# Wireless_thermometer_sensors.net
KiCad netlist of a schematic drawn in Altium Designer
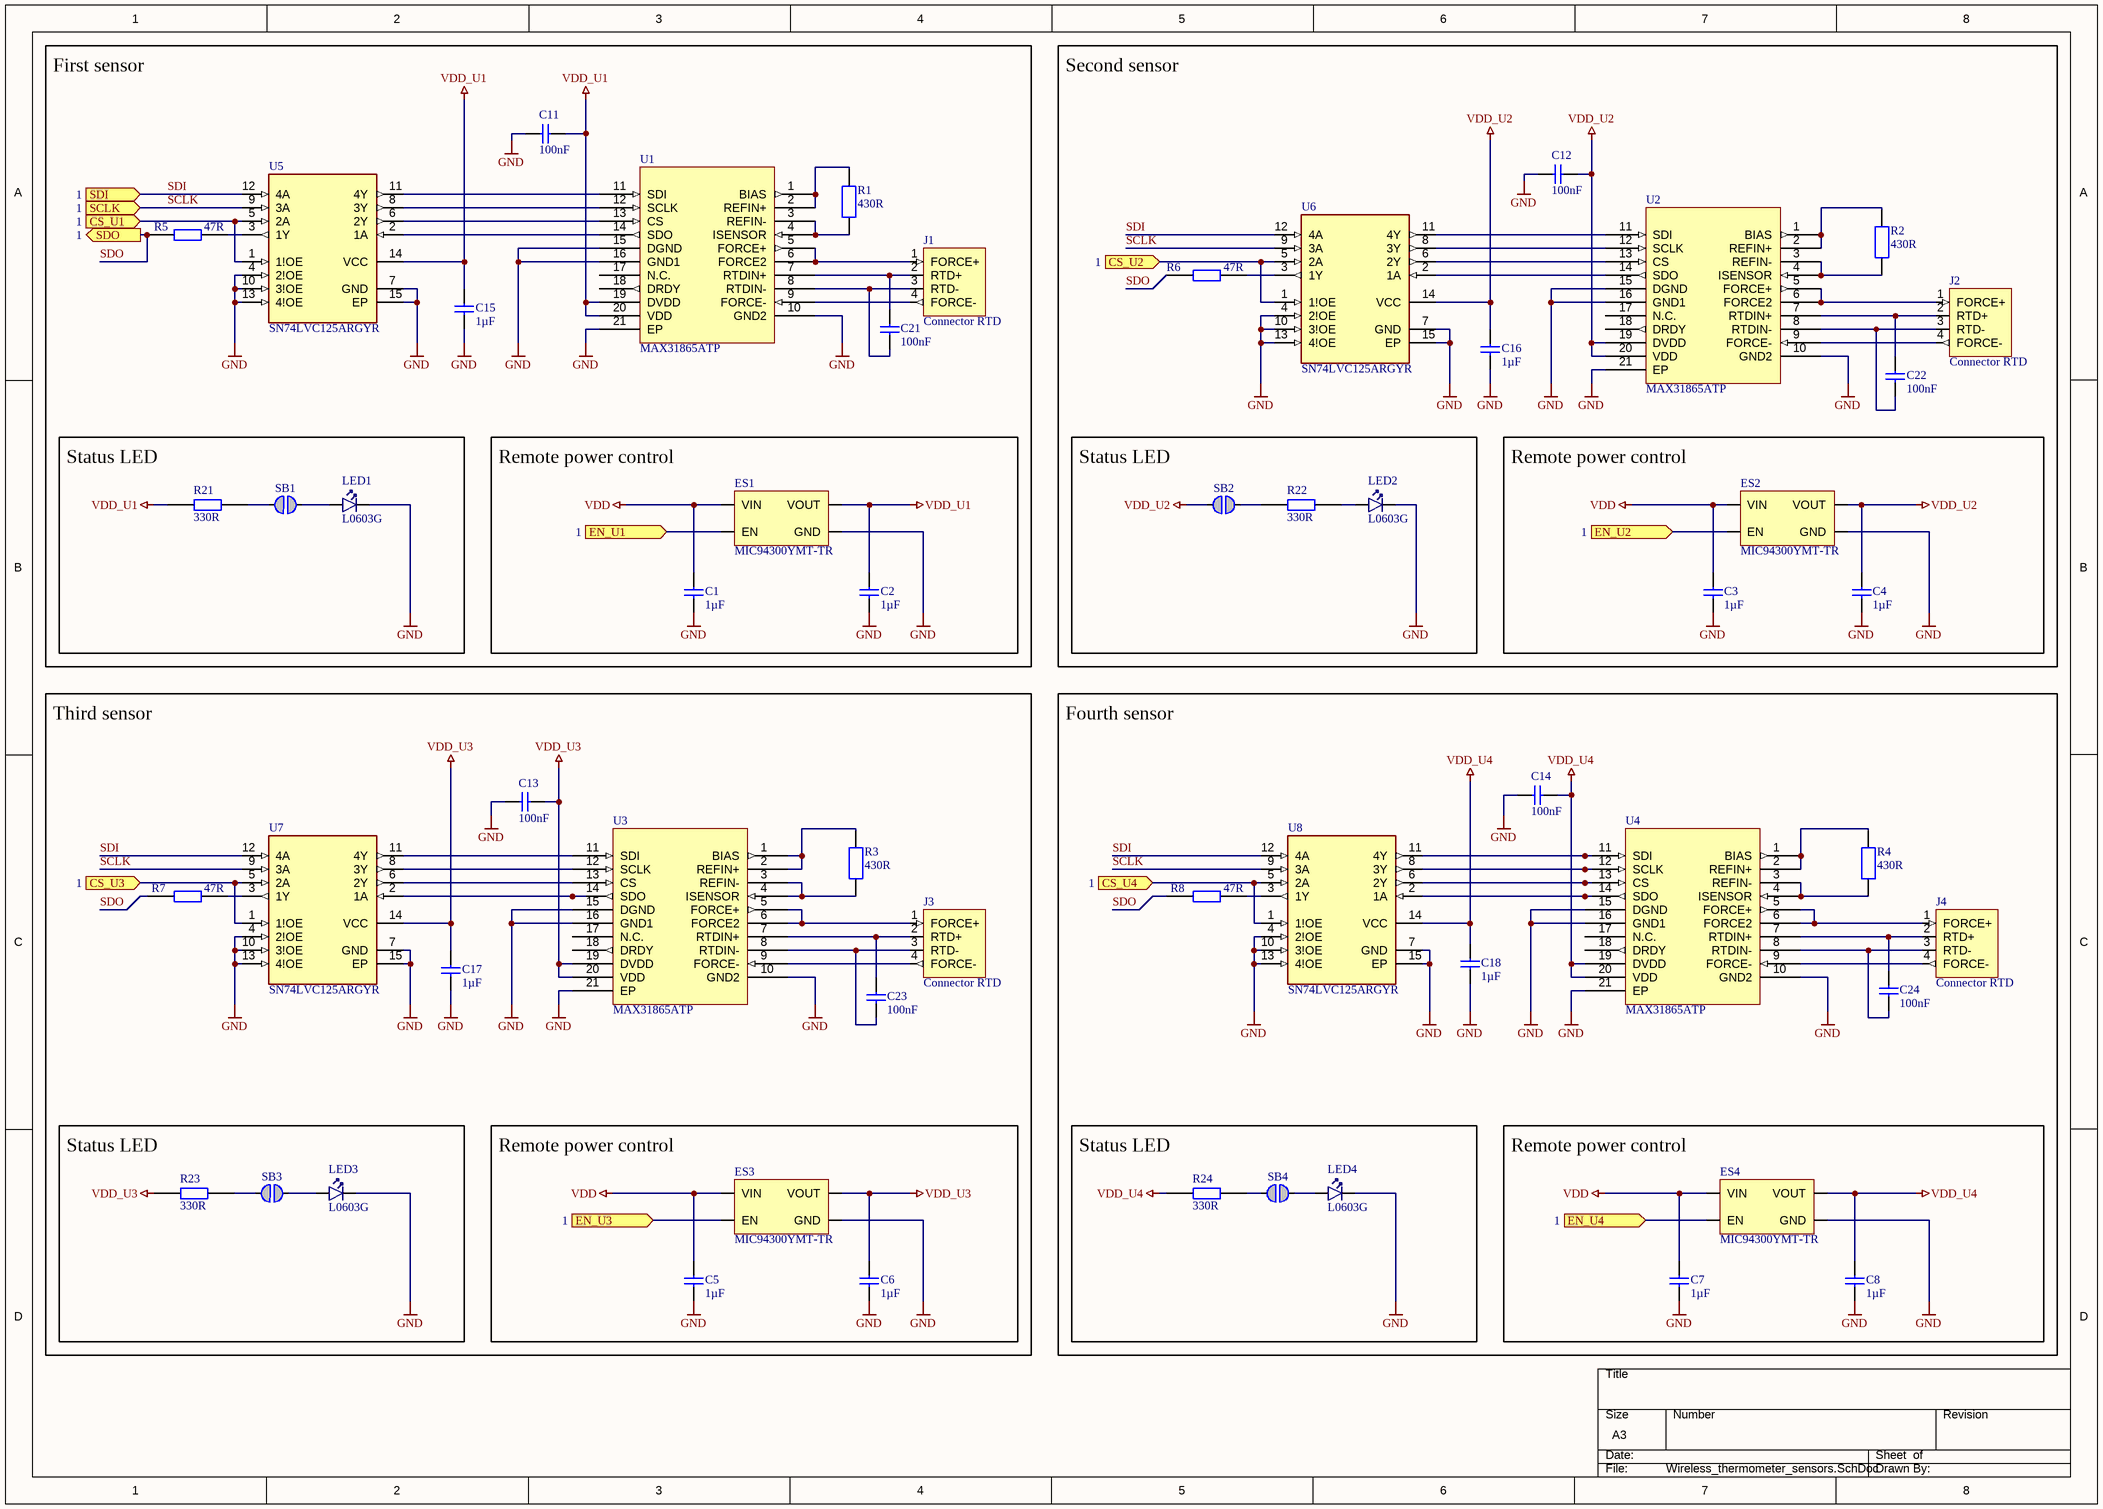
[diagram p0: Wireless_thermometer_sensors.SchDoc]

(export (version "E")
  (design (tool "Eeschema 10.0.6"))
  (components
    (comp (ref "C1")
      (value "1µF")
      (footprint "CAPC1005X04L")
      (description "Capacitor, X7R, ±10%")
      (fields (field (name "PART NUMBER") "C0402-1µ0") (field (name "PUBLISHER") "Nordic Semiconductor"))
      (libsource (lib "Remote_thermometer") (part "CAP_0402"))
    )
    (comp (ref "C2")
      (value "1µF")
      (footprint "CAPC1005X04L")
      (description "Capacitor, X7R, ±10%")
      (fields (field (name "PART NUMBER") "C0402-1µ0") (field (name "PUBLISHER") "Nordic Semiconductor"))
      (libsource (lib "Remote_thermometer") (part "CAP_0402"))
    )
    (comp (ref "C3")
      (value "1µF")
      (footprint "CAPC1005X04L")
      (description "Capacitor, X7R, ±10%")
      (fields (field (name "PART NUMBER") "C0402-1µ0") (field (name "PUBLISHER") "Nordic Semiconductor"))
      (libsource (lib "Remote_thermometer") (part "CAP_0402"))
    )
    (comp (ref "C4")
      (value "1µF")
      (footprint "CAPC1005X04L")
      (description "Capacitor, X7R, ±10%")
      (fields (field (name "PART NUMBER") "C0402-1µ0") (field (name "PUBLISHER") "Nordic Semiconductor"))
      (libsource (lib "Remote_thermometer") (part "CAP_0402"))
    )
    (comp (ref "C5")
      (value "1µF")
      (footprint "CAPC1005X04L")
      (description "Capacitor, X7R, ±10%")
      (fields (field (name "PART NUMBER") "C0402-1µ0") (field (name "PUBLISHER") "Nordic Semiconductor"))
      (libsource (lib "Remote_thermometer") (part "CAP_0402"))
    )
    (comp (ref "C6")
      (value "1µF")
      (footprint "CAPC1005X04L")
      (description "Capacitor, X7R, ±10%")
      (fields (field (name "PART NUMBER") "C0402-1µ0") (field (name "PUBLISHER") "Nordic Semiconductor"))
      (libsource (lib "Remote_thermometer") (part "CAP_0402"))
    )
    (comp (ref "C7")
      (value "1µF")
      (footprint "CAPC1005X04L")
      (description "Capacitor, X7R, ±10%")
      (fields (field (name "PART NUMBER") "C0402-1µ0") (field (name "PUBLISHER") "Nordic Semiconductor"))
      (libsource (lib "Remote_thermometer") (part "CAP_0402"))
    )
    (comp (ref "C8")
      (value "1µF")
      (footprint "CAPC1005X04L")
      (description "Capacitor, X7R, ±10%")
      (fields (field (name "PART NUMBER") "C0402-1µ0") (field (name "PUBLISHER") "Nordic Semiconductor"))
      (libsource (lib "Remote_thermometer") (part "CAP_0402"))
    )
    (comp (ref "C11")
      (value "100nF")
      (footprint "CAPC1005X04L")
      (description "Capacitor, X7R, ±10%")
      (fields (field (name "PART NUMBER") "C0402-1µ0") (field (name "PUBLISHER") "Nordic Semiconductor"))
      (libsource (lib "Remote_thermometer") (part "CAP_0402"))
    )
    (comp (ref "C12")
      (value "100nF")
      (footprint "CAPC1005X04L")
      (description "Capacitor, X7R, ±10%")
      (fields (field (name "PART NUMBER") "C0402-1µ0") (field (name "PUBLISHER") "Nordic Semiconductor"))
      (libsource (lib "Remote_thermometer") (part "CAP_0402"))
    )
    (comp (ref "C13")
      (value "100nF")
      (footprint "CAPC1005X04L")
      (description "Capacitor, X7R, ±10%")
      (fields (field (name "PART NUMBER") "C0402-1µ0") (field (name "PUBLISHER") "Nordic Semiconductor"))
      (libsource (lib "Remote_thermometer") (part "CAP_0402"))
    )
    (comp (ref "C14")
      (value "100nF")
      (footprint "CAPC1005X04L")
      (description "Capacitor, X7R, ±10%")
      (fields (field (name "PART NUMBER") "C0402-1µ0") (field (name "PUBLISHER") "Nordic Semiconductor"))
      (libsource (lib "Remote_thermometer") (part "CAP_0402"))
    )
    (comp (ref "C15")
      (value "1µF")
      (footprint "CAPC1005X04L")
      (description "Capacitor, X7R, ±10%")
      (fields (field (name "PART NUMBER") "C0402-1µ0") (field (name "PUBLISHER") "Nordic Semiconductor"))
      (libsource (lib "Remote_thermometer") (part "CAP_0402"))
    )
    (comp (ref "C16")
      (value "1µF")
      (footprint "CAPC1005X04L")
      (description "Capacitor, X7R, ±10%")
      (fields (field (name "PART NUMBER") "C0402-1µ0") (field (name "PUBLISHER") "Nordic Semiconductor"))
      (libsource (lib "Remote_thermometer") (part "CAP_0402"))
    )
    (comp (ref "C17")
      (value "1µF")
      (footprint "CAPC1005X04L")
      (description "Capacitor, X7R, ±10%")
      (fields (field (name "PART NUMBER") "C0402-1µ0") (field (name "PUBLISHER") "Nordic Semiconductor"))
      (libsource (lib "Remote_thermometer") (part "CAP_0402"))
    )
    (comp (ref "C18")
      (value "1µF")
      (footprint "CAPC1005X04L")
      (description "Capacitor, X7R, ±10%")
      (fields (field (name "PART NUMBER") "C0402-1µ0") (field (name "PUBLISHER") "Nordic Semiconductor"))
      (libsource (lib "Remote_thermometer") (part "CAP_0402"))
    )
    (comp (ref "C21")
      (value "100nF")
      (footprint "CAPC1005X04L")
      (description "Capacitor, X7R, ±10%")
      (fields (field (name "PART NUMBER") "C0402-1µ0") (field (name "PUBLISHER") "Nordic Semiconductor"))
      (libsource (lib "Remote_thermometer") (part "CAP_0402"))
    )
    (comp (ref "C22")
      (value "100nF")
      (footprint "CAPC1005X04L")
      (description "Capacitor, X7R, ±10%")
      (fields (field (name "PART NUMBER") "C0402-1µ0") (field (name "PUBLISHER") "Nordic Semiconductor"))
      (libsource (lib "Remote_thermometer") (part "CAP_0402"))
    )
    (comp (ref "C23")
      (value "100nF")
      (footprint "CAPC1005X04L")
      (description "Capacitor, X7R, ±10%")
      (fields (field (name "PART NUMBER") "C0402-1µ0") (field (name "PUBLISHER") "Nordic Semiconductor"))
      (libsource (lib "Remote_thermometer") (part "CAP_0402"))
    )
    (comp (ref "C24")
      (value "100nF")
      (footprint "CAPC1005X04L")
      (description "Capacitor, X7R, ±10%")
      (fields (field (name "PART NUMBER") "C0402-1µ0") (field (name "PUBLISHER") "Nordic Semiconductor"))
      (libsource (lib "Remote_thermometer") (part "CAP_0402"))
    )
    (comp (ref "ES1")
      (value "MIC94300YMT-TR")
      (footprint "MIC94300YMT-TR")
      (description "MIC94300 Series Single 3.6 V 200 mA Ripple Blocker Technology Load Switch -MLF-4")
      (fields (field (name "MANUFACTURER") "Microchip"))
      (libsource (lib "Remote_thermometer") (part "MIC94300YMT-TR"))
    )
    (comp (ref "ES2")
      (value "MIC94300YMT-TR")
      (footprint "MIC94300YMT-TR")
      (description "MIC94300 Series Single 3.6 V 200 mA Ripple Blocker Technology Load Switch -MLF-4")
      (fields (field (name "MANUFACTURER") "Microchip"))
      (libsource (lib "Remote_thermometer") (part "MIC94300YMT-TR"))
    )
    (comp (ref "ES3")
      (value "MIC94300YMT-TR")
      (footprint "MIC94300YMT-TR")
      (description "MIC94300 Series Single 3.6 V 200 mA Ripple Blocker Technology Load Switch -MLF-4")
      (fields (field (name "MANUFACTURER") "Microchip"))
      (libsource (lib "Remote_thermometer") (part "MIC94300YMT-TR"))
    )
    (comp (ref "ES4")
      (value "MIC94300YMT-TR")
      (footprint "MIC94300YMT-TR")
      (description "MIC94300 Series Single 3.6 V 200 mA Ripple Blocker Technology Load Switch -MLF-4")
      (fields (field (name "MANUFACTURER") "Microchip"))
      (libsource (lib "Remote_thermometer") (part "MIC94300YMT-TR"))
    )
    (comp (ref "J1")
      (value "Connector RTD")
      (footprint "CON-RTD")
      (libsource (lib "Remote_thermometer") (part "CON-RTD"))
    )
    (comp (ref "J2")
      (value "Connector RTD")
      (footprint "CON-RTD")
      (libsource (lib "Remote_thermometer") (part "CON-RTD"))
    )
    (comp (ref "J3")
      (value "Connector RTD")
      (footprint "CON-RTD")
      (libsource (lib "Remote_thermometer") (part "CON-RTD"))
    )
    (comp (ref "J4")
      (value "Connector RTD")
      (footprint "CON-RTD")
      (libsource (lib "Remote_thermometer") (part "CON-RTD"))
    )
    (comp (ref "LED1")
      (value "L0603G")
      (footprint "LED_0603_G")
      (description "LED, Green, 0603, 573nm, Vf=2.0V, 24mcd, - 40 to +85°C")
      (fields
        (field (name "PART NUMBER") "VS 25C7M5")
        (field (name "MANUFACTURER") "Victory Electronics")
        (field (name "PUBLISHER") "Nordic Semiconductor")
      )
      (libsource (lib "Remote_thermometer") (part "D{colon}LED"))
    )
    (comp (ref "LED2")
      (value "L0603G")
      (footprint "LED_0603_G")
      (description "LED, Green, 0603, 573nm, Vf=2.0V, 24mcd, - 40 to +85°C")
      (fields
        (field (name "PART NUMBER") "VS 25C7M5")
        (field (name "MANUFACTURER") "Victory Electronics")
        (field (name "PUBLISHER") "Nordic Semiconductor")
      )
      (libsource (lib "Remote_thermometer") (part "D{colon}LED"))
    )
    (comp (ref "LED3")
      (value "L0603G")
      (footprint "LED_0603_G")
      (description "LED, Green, 0603, 573nm, Vf=2.0V, 24mcd, - 40 to +85°C")
      (fields
        (field (name "PART NUMBER") "VS 25C7M5")
        (field (name "MANUFACTURER") "Victory Electronics")
        (field (name "PUBLISHER") "Nordic Semiconductor")
      )
      (libsource (lib "Remote_thermometer") (part "D{colon}LED"))
    )
    (comp (ref "LED4")
      (value "L0603G")
      (footprint "LED_0603_G")
      (description "LED, Green, 0603, 573nm, Vf=2.0V, 24mcd, - 40 to +85°C")
      (fields
        (field (name "PART NUMBER") "VS 25C7M5")
        (field (name "MANUFACTURER") "Victory Electronics")
        (field (name "PUBLISHER") "Nordic Semiconductor")
      )
      (libsource (lib "Remote_thermometer") (part "D{colon}LED"))
    )
    (comp (ref "R1")
      (value "430R")
      (footprint "RESR1608X06")
      (description "Resistor")
      (fields (field (name "PART NUMBER") "R0603-430R") (field (name "PUBLISHER") "Nordic Semiconductor"))
      (libsource (lib "Remote_thermometer") (part "RES_0603"))
    )
    (comp (ref "R2")
      (value "430R")
      (footprint "RESR1608X06")
      (description "Resistor")
      (fields (field (name "PART NUMBER") "R0603-430R") (field (name "PUBLISHER") "Nordic Semiconductor"))
      (libsource (lib "Remote_thermometer") (part "RES_0603"))
    )
    (comp (ref "R3")
      (value "430R")
      (footprint "RESR1608X06")
      (description "Resistor")
      (fields (field (name "PART NUMBER") "R0603-430R") (field (name "PUBLISHER") "Nordic Semiconductor"))
      (libsource (lib "Remote_thermometer") (part "RES_0603"))
    )
    (comp (ref "R4")
      (value "430R")
      (footprint "RESR1608X06")
      (description "Resistor")
      (fields (field (name "PART NUMBER") "R0603-430R") (field (name "PUBLISHER") "Nordic Semiconductor"))
      (libsource (lib "Remote_thermometer") (part "RES_0603"))
    )
    (comp (ref "R5")
      (value "47R")
      (footprint "RESC1005X04L")
      (description "Resistor")
      (fields (field (name "PART NUMBER") "R0603-430R") (field (name "PUBLISHER") "Nordic Semiconductor"))
      (libsource (lib "Remote_thermometer") (part "RES_0402"))
    )
    (comp (ref "R6")
      (value "47R")
      (footprint "RESC1005X04L")
      (description "Resistor")
      (fields (field (name "PART NUMBER") "R0603-430R") (field (name "PUBLISHER") "Nordic Semiconductor"))
      (libsource (lib "Remote_thermometer") (part "RES_0402"))
    )
    (comp (ref "R7")
      (value "47R")
      (footprint "RESC1005X04L")
      (description "Resistor")
      (fields (field (name "PART NUMBER") "R0603-430R") (field (name "PUBLISHER") "Nordic Semiconductor"))
      (libsource (lib "Remote_thermometer") (part "RES_0402"))
    )
    (comp (ref "R8")
      (value "47R")
      (footprint "RESC1005X04L")
      (description "Resistor")
      (fields (field (name "PART NUMBER") "R0603-430R") (field (name "PUBLISHER") "Nordic Semiconductor"))
      (libsource (lib "Remote_thermometer") (part "RES_0402"))
    )
    (comp (ref "R21")
      (value "330R")
      (footprint "RESC1005X04L")
      (description "Resistor")
      (fields (field (name "PART NUMBER") "R0603-430R") (field (name "PUBLISHER") "Nordic Semiconductor"))
      (libsource (lib "Remote_thermometer") (part "RES_0402"))
    )
    (comp (ref "R22")
      (value "330R")
      (footprint "RESC1005X04L")
      (description "Resistor")
      (fields (field (name "PART NUMBER") "R0603-430R") (field (name "PUBLISHER") "Nordic Semiconductor"))
      (libsource (lib "Remote_thermometer") (part "RES_0402"))
    )
    (comp (ref "R23")
      (value "330R")
      (footprint "RESC1005X04L")
      (description "Resistor")
      (fields (field (name "PART NUMBER") "R0603-430R") (field (name "PUBLISHER") "Nordic Semiconductor"))
      (libsource (lib "Remote_thermometer") (part "RES_0402"))
    )
    (comp (ref "R24")
      (value "330R")
      (footprint "RESC1005X04L")
      (description "Resistor")
      (fields (field (name "PART NUMBER") "R0603-430R") (field (name "PUBLISHER") "Nordic Semiconductor"))
      (libsource (lib "Remote_thermometer") (part "RES_0402"))
    )
    (comp (ref "SB1")
      (value "Solderbridge")
      (footprint "Solderbridge")
      (fields (field (name "PUBLISHER") "Nordic Semiconductor"))
      (libsource (lib "Remote_thermometer") (part "SOLDERBRIDGE"))
    )
    (comp (ref "SB2")
      (value "Solderbridge")
      (footprint "Solderbridge")
      (fields (field (name "PUBLISHER") "Nordic Semiconductor"))
      (libsource (lib "Remote_thermometer") (part "SOLDERBRIDGE"))
    )
    (comp (ref "SB3")
      (value "Solderbridge")
      (footprint "Solderbridge")
      (fields (field (name "PUBLISHER") "Nordic Semiconductor"))
      (libsource (lib "Remote_thermometer") (part "SOLDERBRIDGE"))
    )
    (comp (ref "SB4")
      (value "Solderbridge")
      (footprint "Solderbridge")
      (fields (field (name "PUBLISHER") "Nordic Semiconductor"))
      (libsource (lib "Remote_thermometer") (part "SOLDERBRIDGE"))
    )
    (comp (ref "U1")
      (value "MAX31865ATP")
      (footprint "21-0140L_T2055-5_MXM-L")
      (description "Circuit Protection Misc Resistance Temperature Detector to Digital Converter")
      (fields (field (name "MANUFACTURER") "Maxim") (field (name "MANUFACTURER PART NUMBER") "MAX31865ATP+T"))
      (libsource (lib "Remote_thermometer") (part "MAX31865ATP"))
    )
    (comp (ref "U2")
      (value "MAX31865ATP")
      (footprint "21-0140L_T2055-5_MXM-L")
      (description "Circuit Protection Misc Resistance Temperature Detector to Digital Converter")
      (fields (field (name "MANUFACTURER") "Maxim") (field (name "MANUFACTURER PART NUMBER") "MAX31865ATP+T"))
      (libsource (lib "Remote_thermometer") (part "MAX31865ATP"))
    )
    (comp (ref "U3")
      (value "MAX31865ATP")
      (footprint "21-0140L_T2055-5_MXM-L")
      (description "Circuit Protection Misc Resistance Temperature Detector to Digital Converter")
      (fields (field (name "MANUFACTURER") "Maxim") (field (name "MANUFACTURER PART NUMBER") "MAX31865ATP+T"))
      (libsource (lib "Remote_thermometer") (part "MAX31865ATP"))
    )
    (comp (ref "U4")
      (value "MAX31865ATP")
      (footprint "21-0140L_T2055-5_MXM-L")
      (description "Circuit Protection Misc Resistance Temperature Detector to Digital Converter")
      (fields (field (name "MANUFACTURER") "Maxim") (field (name "MANUFACTURER PART NUMBER") "MAX31865ATP+T"))
      (libsource (lib "Remote_thermometer") (part "MAX31865ATP"))
    )
    (comp (ref "U5")
      (value "SN74LVC125ARGYR")
      (footprint "QFN50P350X350X100-15N")
      (description "Quadruple Bus Buffer Gate With 3-State Outputs 14-VQFN -40 to 125")
      (libsource (lib "Remote_thermometer") (part "SN74LVC125ARGYR"))
    )
    (comp (ref "U6")
      (value "SN74LVC125ARGYR")
      (footprint "QFN50P350X350X100-15N")
      (description "Quadruple Bus Buffer Gate With 3-State Outputs 14-VQFN -40 to 125")
      (libsource (lib "Remote_thermometer") (part "SN74LVC125ARGYR"))
    )
    (comp (ref "U7")
      (value "SN74LVC125ARGYR")
      (footprint "QFN50P350X350X100-15N")
      (description "Quadruple Bus Buffer Gate With 3-State Outputs 14-VQFN -40 to 125")
      (libsource (lib "Remote_thermometer") (part "SN74LVC125ARGYR"))
    )
    (comp (ref "U8")
      (value "SN74LVC125ARGYR")
      (footprint "QFN50P350X350X100-15N")
      (description "Quadruple Bus Buffer Gate With 3-State Outputs 14-VQFN -40 to 125")
      (libsource (lib "Remote_thermometer") (part "SN74LVC125ARGYR"))
    )
  )
  (nets
    (net (code "1") (name "/CS_U1") (class "Default")
      (node (ref "U5") (pin "1") (pinfunction "1!OE_1") (pintype "input"))
      (node (ref "U5") (pin "5") (pinfunction "2A_5") (pintype "input"))
    )
    (net (code "2") (name "/CS_U2") (class "Default")
      (node (ref "U6") (pin "1") (pinfunction "1!OE_1") (pintype "input"))
      (node (ref "U6") (pin "5") (pinfunction "2A_5") (pintype "input"))
    )
    (net (code "3") (name "/CS_U3") (class "Default")
      (node (ref "U7") (pin "1") (pinfunction "1!OE_1") (pintype "input"))
      (node (ref "U7") (pin "5") (pinfunction "2A_5") (pintype "input"))
    )
    (net (code "4") (name "/CS_U4") (class "Default")
      (node (ref "U8") (pin "1") (pinfunction "1!OE_1") (pintype "input"))
      (node (ref "U8") (pin "5") (pinfunction "2A_5") (pintype "input"))
    )
    (net (code "5") (name "/EN_U1") (class "Default")
      (node (ref "ES1") (pin "1") (pinfunction "EN_1") (pintype "passive"))
    )
    (net (code "6") (name "/EN_U2") (class "Default")
      (node (ref "ES2") (pin "1") (pinfunction "EN_1") (pintype "passive"))
    )
    (net (code "7") (name "/EN_U3") (class "Default")
      (node (ref "ES3") (pin "1") (pinfunction "EN_1") (pintype "passive"))
    )
    (net (code "8") (name "/EN_U4") (class "Default")
      (node (ref "ES4") (pin "1") (pinfunction "EN_1") (pintype "passive"))
    )
    (net (code "9") (name "/SCLK") (class "Default")
      (node (ref "U5") (pin "9") (pinfunction "3A_9") (pintype "input"))
      (node (ref "U6") (pin "9") (pinfunction "3A_9") (pintype "input"))
      (node (ref "U7") (pin "9") (pinfunction "3A_9") (pintype "input"))
      (node (ref "U8") (pin "9") (pinfunction "3A_9") (pintype "input"))
    )
    (net (code "10") (name "/SDI") (class "Default")
      (node (ref "U5") (pin "12") (pinfunction "4A_12") (pintype "input"))
      (node (ref "U6") (pin "12") (pinfunction "4A_12") (pintype "input"))
      (node (ref "U7") (pin "12") (pinfunction "4A_12") (pintype "input"))
      (node (ref "U8") (pin "12") (pinfunction "4A_12") (pintype "input"))
    )
    (net (code "11") (name "/SDO") (class "Default")
      (node (ref "R5") (pin "1") (pinfunction "1_1") (pintype "passive"))
      (node (ref "R6") (pin "1") (pinfunction "1_1") (pintype "passive"))
      (node (ref "R7") (pin "1") (pinfunction "1_1") (pintype "passive"))
      (node (ref "R8") (pin "1") (pinfunction "1_1") (pintype "passive"))
    )
    (net (code "12") (name "GND") (class "Default")
      (node (ref "C1") (pin "1") (pinfunction "1_1") (pintype "passive"))
      (node (ref "C11") (pin "1") (pinfunction "1_1") (pintype "passive"))
      (node (ref "C12") (pin "1") (pinfunction "1_1") (pintype "passive"))
      (node (ref "C13") (pin "2") (pinfunction "2_2") (pintype "passive"))
      (node (ref "C14") (pin "1") (pinfunction "1_1") (pintype "passive"))
      (node (ref "C15") (pin "1") (pinfunction "1_1") (pintype "passive"))
      (node (ref "C16") (pin "1") (pinfunction "1_1") (pintype "passive"))
      (node (ref "C17") (pin "1") (pinfunction "1_1") (pintype "passive"))
      (node (ref "C18") (pin "1") (pinfunction "1_1") (pintype "passive"))
      (node (ref "C2") (pin "1") (pinfunction "1_1") (pintype "passive"))
      (node (ref "C3") (pin "1") (pinfunction "1_1") (pintype "passive"))
      (node (ref "C4") (pin "1") (pinfunction "1_1") (pintype "passive"))
      (node (ref "C5") (pin "1") (pinfunction "1_1") (pintype "passive"))
      (node (ref "C6") (pin "1") (pinfunction "1_1") (pintype "passive"))
      (node (ref "C7") (pin "1") (pinfunction "1_1") (pintype "passive"))
      (node (ref "C8") (pin "1") (pinfunction "1_1") (pintype "passive"))
      (node (ref "ES1") (pin "2") (pinfunction "GND_2") (pintype "passive"))
      (node (ref "ES2") (pin "2") (pinfunction "GND_2") (pintype "passive"))
      (node (ref "ES3") (pin "2") (pinfunction "GND_2") (pintype "passive"))
      (node (ref "ES4") (pin "2") (pinfunction "GND_2") (pintype "passive"))
      (node (ref "LED1") (pin "1") (pinfunction "C_1") (pintype "passive"))
      (node (ref "LED2") (pin "1") (pinfunction "C_1") (pintype "passive"))
      (node (ref "LED3") (pin "1") (pinfunction "C_1") (pintype "passive"))
      (node (ref "LED4") (pin "1") (pinfunction "C_1") (pintype "passive"))
      (node (ref "U1") (pin "10") (pinfunction "GND2_10") (pintype "passive"))
      (node (ref "U1") (pin "15") (pinfunction "DGND_15") (pintype "passive"))
      (node (ref "U1") (pin "16") (pinfunction "GND1_16") (pintype "passive"))
      (node (ref "U1") (pin "21") (pinfunction "EP_21") (pintype "passive"))
      (node (ref "U2") (pin "10") (pinfunction "GND2_10") (pintype "passive"))
      (node (ref "U2") (pin "15") (pinfunction "DGND_15") (pintype "passive"))
      (node (ref "U2") (pin "16") (pinfunction "GND1_16") (pintype "passive"))
      (node (ref "U2") (pin "21") (pinfunction "EP_21") (pintype "passive"))
      (node (ref "U3") (pin "10") (pinfunction "GND2_10") (pintype "passive"))
      (node (ref "U3") (pin "15") (pinfunction "DGND_15") (pintype "passive"))
      (node (ref "U3") (pin "16") (pinfunction "GND1_16") (pintype "passive"))
      (node (ref "U3") (pin "21") (pinfunction "EP_21") (pintype "passive"))
      (node (ref "U4") (pin "10") (pinfunction "GND2_10") (pintype "passive"))
      (node (ref "U4") (pin "15") (pinfunction "DGND_15") (pintype "passive"))
      (node (ref "U4") (pin "16") (pinfunction "GND1_16") (pintype "passive"))
      (node (ref "U4") (pin "21") (pinfunction "EP_21") (pintype "passive"))
      (node (ref "U5") (pin "10") (pinfunction "3!OE_10") (pintype "input"))
      (node (ref "U5") (pin "13") (pinfunction "4!OE_13") (pintype "input"))
      (node (ref "U5") (pin "15") (pinfunction "EP_15") (pintype "power_in"))
      (node (ref "U5") (pin "4") (pinfunction "2!OE_4") (pintype "input"))
      (node (ref "U5") (pin "7") (pinfunction "GND_7") (pintype "power_in"))
      (node (ref "U6") (pin "10") (pinfunction "3!OE_10") (pintype "input"))
      (node (ref "U6") (pin "13") (pinfunction "4!OE_13") (pintype "input"))
      (node (ref "U6") (pin "15") (pinfunction "EP_15") (pintype "power_in"))
      (node (ref "U6") (pin "4") (pinfunction "2!OE_4") (pintype "input"))
      (node (ref "U6") (pin "7") (pinfunction "GND_7") (pintype "power_in"))
      (node (ref "U7") (pin "10") (pinfunction "3!OE_10") (pintype "input"))
      (node (ref "U7") (pin "13") (pinfunction "4!OE_13") (pintype "input"))
      (node (ref "U7") (pin "15") (pinfunction "EP_15") (pintype "power_in"))
      (node (ref "U7") (pin "4") (pinfunction "2!OE_4") (pintype "input"))
      (node (ref "U7") (pin "7") (pinfunction "GND_7") (pintype "power_in"))
      (node (ref "U8") (pin "10") (pinfunction "3!OE_10") (pintype "input"))
      (node (ref "U8") (pin "13") (pinfunction "4!OE_13") (pintype "input"))
      (node (ref "U8") (pin "15") (pinfunction "EP_15") (pintype "power_in"))
      (node (ref "U8") (pin "4") (pinfunction "2!OE_4") (pintype "input"))
      (node (ref "U8") (pin "7") (pinfunction "GND_7") (pintype "power_in"))
    )
    (net (code "13") (name "Net-(J1-FORCE+)") (class "Default")
      (node (ref "J1") (pin "1") (pinfunction "FORCE+_1") (pintype "input"))
      (node (ref "U1") (pin "5") (pinfunction "FORCE+_5") (pintype "output"))
      (node (ref "U1") (pin "6") (pinfunction "FORCE2_6") (pintype "passive"))
    )
    (net (code "14") (name "Net-(J1-FORCE-)") (class "Default")
      (node (ref "J1") (pin "4") (pinfunction "FORCE-_4") (pintype "output"))
      (node (ref "U1") (pin "9") (pinfunction "FORCE-_9") (pintype "input"))
    )
    (net (code "15") (name "Net-(J1-RTD+)") (class "Default")
      (node (ref "C21") (pin "2") (pinfunction "2_2") (pintype "passive"))
      (node (ref "J1") (pin "2") (pinfunction "RTD+_2") (pintype "passive"))
      (node (ref "U1") (pin "7") (pinfunction "RTDIN+_7") (pintype "passive"))
    )
    (net (code "16") (name "Net-(J1-RTD-)") (class "Default")
      (node (ref "C21") (pin "1") (pinfunction "1_1") (pintype "passive"))
      (node (ref "J1") (pin "3") (pinfunction "RTD-_3") (pintype "passive"))
      (node (ref "U1") (pin "8") (pinfunction "RTDIN-_8") (pintype "passive"))
    )
    (net (code "17") (name "Net-(J2-FORCE+)") (class "Default")
      (node (ref "J2") (pin "1") (pinfunction "FORCE+_1") (pintype "input"))
      (node (ref "U2") (pin "5") (pinfunction "FORCE+_5") (pintype "output"))
      (node (ref "U2") (pin "6") (pinfunction "FORCE2_6") (pintype "passive"))
    )
    (net (code "18") (name "Net-(J2-FORCE-)") (class "Default")
      (node (ref "J2") (pin "4") (pinfunction "FORCE-_4") (pintype "output"))
      (node (ref "U2") (pin "9") (pinfunction "FORCE-_9") (pintype "input"))
    )
    (net (code "19") (name "Net-(J2-RTD+)") (class "Default")
      (node (ref "C22") (pin "2") (pinfunction "2_2") (pintype "passive"))
      (node (ref "J2") (pin "2") (pinfunction "RTD+_2") (pintype "passive"))
      (node (ref "U2") (pin "7") (pinfunction "RTDIN+_7") (pintype "passive"))
    )
    (net (code "20") (name "Net-(J2-RTD-)") (class "Default")
      (node (ref "C22") (pin "1") (pinfunction "1_1") (pintype "passive"))
      (node (ref "J2") (pin "3") (pinfunction "RTD-_3") (pintype "passive"))
      (node (ref "U2") (pin "8") (pinfunction "RTDIN-_8") (pintype "passive"))
    )
    (net (code "21") (name "Net-(J3-FORCE+)") (class "Default")
      (node (ref "J3") (pin "1") (pinfunction "FORCE+_1") (pintype "input"))
      (node (ref "U3") (pin "5") (pinfunction "FORCE+_5") (pintype "output"))
      (node (ref "U3") (pin "6") (pinfunction "FORCE2_6") (pintype "passive"))
    )
    (net (code "22") (name "Net-(J3-FORCE-)") (class "Default")
      (node (ref "J3") (pin "4") (pinfunction "FORCE-_4") (pintype "output"))
      (node (ref "U3") (pin "9") (pinfunction "FORCE-_9") (pintype "input"))
    )
    (net (code "23") (name "Net-(J3-RTD+)") (class "Default")
      (node (ref "C23") (pin "2") (pinfunction "2_2") (pintype "passive"))
      (node (ref "J3") (pin "2") (pinfunction "RTD+_2") (pintype "passive"))
      (node (ref "U3") (pin "7") (pinfunction "RTDIN+_7") (pintype "passive"))
    )
    (net (code "24") (name "Net-(J3-RTD-)") (class "Default")
      (node (ref "C23") (pin "1") (pinfunction "1_1") (pintype "passive"))
      (node (ref "J3") (pin "3") (pinfunction "RTD-_3") (pintype "passive"))
      (node (ref "U3") (pin "8") (pinfunction "RTDIN-_8") (pintype "passive"))
    )
    (net (code "25") (name "Net-(J4-FORCE+)") (class "Default")
      (node (ref "J4") (pin "1") (pinfunction "FORCE+_1") (pintype "input"))
      (node (ref "U4") (pin "5") (pinfunction "FORCE+_5") (pintype "output"))
      (node (ref "U4") (pin "6") (pinfunction "FORCE2_6") (pintype "passive"))
    )
    (net (code "26") (name "Net-(J4-FORCE-)") (class "Default")
      (node (ref "J4") (pin "4") (pinfunction "FORCE-_4") (pintype "output"))
      (node (ref "U4") (pin "9") (pinfunction "FORCE-_9") (pintype "input"))
    )
    (net (code "27") (name "Net-(J4-RTD+)") (class "Default")
      (node (ref "C24") (pin "2") (pinfunction "2_2") (pintype "passive"))
      (node (ref "J4") (pin "2") (pinfunction "RTD+_2") (pintype "passive"))
      (node (ref "U4") (pin "7") (pinfunction "RTDIN+_7") (pintype "passive"))
    )
    (net (code "28") (name "Net-(J4-RTD-)") (class "Default")
      (node (ref "C24") (pin "1") (pinfunction "1_1") (pintype "passive"))
      (node (ref "J4") (pin "3") (pinfunction "RTD-_3") (pintype "passive"))
      (node (ref "U4") (pin "8") (pinfunction "RTDIN-_8") (pintype "passive"))
    )
    (net (code "29") (name "Net-(LED1-A)") (class "Default")
      (node (ref "LED1") (pin "2") (pinfunction "A_2") (pintype "passive"))
      (node (ref "SB1") (pin "1") (pinfunction "0_1") (pintype "passive"))
    )
    (net (code "30") (name "Net-(LED2-A)") (class "Default")
      (node (ref "LED2") (pin "2") (pinfunction "A_2") (pintype "passive"))
      (node (ref "R22") (pin "2") (pinfunction "2_2") (pintype "passive"))
    )
    (net (code "31") (name "Net-(LED3-A)") (class "Default")
      (node (ref "LED3") (pin "2") (pinfunction "A_2") (pintype "passive"))
      (node (ref "SB3") (pin "1") (pinfunction "0_1") (pintype "passive"))
    )
    (net (code "32") (name "Net-(LED4-A)") (class "Default")
      (node (ref "LED4") (pin "2") (pinfunction "A_2") (pintype "passive"))
      (node (ref "SB4") (pin "1") (pinfunction "0_1") (pintype "passive"))
    )
    (net (code "33") (name "Net-(SB1-1)") (class "Default")
      (node (ref "R21") (pin "2") (pinfunction "2_2") (pintype "passive"))
      (node (ref "SB1") (pin "2") (pinfunction "1_2") (pintype "passive"))
    )
    (net (code "34") (name "Net-(SB2-0)") (class "Default")
      (node (ref "R22") (pin "1") (pinfunction "1_1") (pintype "passive"))
      (node (ref "SB2") (pin "1") (pinfunction "0_1") (pintype "passive"))
    )
    (net (code "35") (name "Net-(SB3-1)") (class "Default")
      (node (ref "R23") (pin "2") (pinfunction "2_2") (pintype "passive"))
      (node (ref "SB3") (pin "2") (pinfunction "1_2") (pintype "passive"))
    )
    (net (code "36") (name "Net-(SB4-1)") (class "Default")
      (node (ref "R24") (pin "2") (pinfunction "2_2") (pintype "passive"))
      (node (ref "SB4") (pin "2") (pinfunction "1_2") (pintype "passive"))
    )
    (net (code "37") (name "Net-(U1-BIAS)") (class "Default")
      (node (ref "R1") (pin "2") (pinfunction "2_2") (pintype "passive"))
      (node (ref "U1") (pin "1") (pinfunction "BIAS_1") (pintype "output"))
      (node (ref "U1") (pin "2") (pinfunction "REFIN+_2") (pintype "passive"))
    )
    (net (code "38") (name "Net-(U1-CS)") (class "Default")
      (node (ref "U1") (pin "13") (pinfunction "CS_13") (pintype "input"))
      (node (ref "U5") (pin "6") (pinfunction "2Y_6") (pintype "output"))
    )
    (net (code "39") (name "Net-(U1-ISENSOR)") (class "Default")
      (node (ref "R1") (pin "1") (pinfunction "1_1") (pintype "passive"))
      (node (ref "U1") (pin "3") (pinfunction "REFIN-_3") (pintype "passive"))
      (node (ref "U1") (pin "4") (pinfunction "ISENSOR_4") (pintype "input"))
    )
    (net (code "40") (name "Net-(U1-SCLK)") (class "Default")
      (node (ref "U1") (pin "12") (pinfunction "SCLK_12") (pintype "input"))
      (node (ref "U5") (pin "8") (pinfunction "3Y_8") (pintype "output"))
    )
    (net (code "41") (name "Net-(U1-SDI)") (class "Default")
      (node (ref "U1") (pin "11") (pinfunction "SDI_11") (pintype "input"))
      (node (ref "U5") (pin "11") (pinfunction "4Y_11") (pintype "output"))
    )
    (net (code "42") (name "Net-(U1-SDO)") (class "Default")
      (node (ref "U1") (pin "14") (pinfunction "SDO_14") (pintype "output"))
      (node (ref "U5") (pin "2") (pinfunction "1A_2") (pintype "input"))
    )
    (net (code "43") (name "Net-(U2-BIAS)") (class "Default")
      (node (ref "R2") (pin "2") (pinfunction "2_2") (pintype "passive"))
      (node (ref "U2") (pin "1") (pinfunction "BIAS_1") (pintype "output"))
      (node (ref "U2") (pin "2") (pinfunction "REFIN+_2") (pintype "passive"))
    )
    (net (code "44") (name "Net-(U2-CS)") (class "Default")
      (node (ref "U2") (pin "13") (pinfunction "CS_13") (pintype "input"))
      (node (ref "U6") (pin "6") (pinfunction "2Y_6") (pintype "output"))
    )
    (net (code "45") (name "Net-(U2-ISENSOR)") (class "Default")
      (node (ref "R2") (pin "1") (pinfunction "1_1") (pintype "passive"))
      (node (ref "U2") (pin "3") (pinfunction "REFIN-_3") (pintype "passive"))
      (node (ref "U2") (pin "4") (pinfunction "ISENSOR_4") (pintype "input"))
    )
    (net (code "46") (name "Net-(U2-SCLK)") (class "Default")
      (node (ref "U2") (pin "12") (pinfunction "SCLK_12") (pintype "input"))
      (node (ref "U6") (pin "8") (pinfunction "3Y_8") (pintype "output"))
    )
    (net (code "47") (name "Net-(U2-SDI)") (class "Default")
      (node (ref "U2") (pin "11") (pinfunction "SDI_11") (pintype "input"))
      (node (ref "U6") (pin "11") (pinfunction "4Y_11") (pintype "output"))
    )
    (net (code "48") (name "Net-(U2-SDO)") (class "Default")
      (node (ref "U2") (pin "14") (pinfunction "SDO_14") (pintype "output"))
      (node (ref "U6") (pin "2") (pinfunction "1A_2") (pintype "input"))
    )
    (net (code "49") (name "Net-(U3-BIAS)") (class "Default")
      (node (ref "R3") (pin "2") (pinfunction "2_2") (pintype "passive"))
      (node (ref "U3") (pin "1") (pinfunction "BIAS_1") (pintype "output"))
      (node (ref "U3") (pin "2") (pinfunction "REFIN+_2") (pintype "passive"))
    )
    (net (code "50") (name "Net-(U3-CS)") (class "Default")
      (node (ref "U3") (pin "13") (pinfunction "CS_13") (pintype "input"))
      (node (ref "U7") (pin "6") (pinfunction "2Y_6") (pintype "output"))
    )
    (net (code "51") (name "Net-(U3-ISENSOR)") (class "Default")
      (node (ref "R3") (pin "1") (pinfunction "1_1") (pintype "passive"))
      (node (ref "U3") (pin "3") (pinfunction "REFIN-_3") (pintype "passive"))
      (node (ref "U3") (pin "4") (pinfunction "ISENSOR_4") (pintype "input"))
    )
    (net (code "52") (name "Net-(U3-SCLK)") (class "Default")
      (node (ref "U3") (pin "12") (pinfunction "SCLK_12") (pintype "input"))
      (node (ref "U7") (pin "8") (pinfunction "3Y_8") (pintype "output"))
    )
    (net (code "53") (name "Net-(U3-SDI)") (class "Default")
      (node (ref "U3") (pin "11") (pinfunction "SDI_11") (pintype "input"))
      (node (ref "U7") (pin "11") (pinfunction "4Y_11") (pintype "output"))
    )
    (net (code "54") (name "Net-(U3-SDO)") (class "Default")
      (node (ref "U3") (pin "14") (pinfunction "SDO_14") (pintype "output"))
      (node (ref "U7") (pin "2") (pinfunction "1A_2") (pintype "input"))
    )
    (net (code "55") (name "Net-(U4-BIAS)") (class "Default")
      (node (ref "R4") (pin "2") (pinfunction "2_2") (pintype "passive"))
      (node (ref "U4") (pin "1") (pinfunction "BIAS_1") (pintype "output"))
      (node (ref "U4") (pin "2") (pinfunction "REFIN+_2") (pintype "passive"))
    )
    (net (code "56") (name "Net-(U4-CS)") (class "Default")
      (node (ref "U4") (pin "13") (pinfunction "CS_13") (pintype "input"))
      (node (ref "U8") (pin "6") (pinfunction "2Y_6") (pintype "output"))
    )
    (net (code "57") (name "Net-(U4-ISENSOR)") (class "Default")
      (node (ref "R4") (pin "1") (pinfunction "1_1") (pintype "passive"))
      (node (ref "U4") (pin "3") (pinfunction "REFIN-_3") (pintype "passive"))
      (node (ref "U4") (pin "4") (pinfunction "ISENSOR_4") (pintype "input"))
    )
    (net (code "58") (name "Net-(U4-SCLK)") (class "Default")
      (node (ref "U4") (pin "12") (pinfunction "SCLK_12") (pintype "input"))
      (node (ref "U8") (pin "8") (pinfunction "3Y_8") (pintype "output"))
    )
    (net (code "59") (name "Net-(U4-SDI)") (class "Default")
      (node (ref "U4") (pin "11") (pinfunction "SDI_11") (pintype "input"))
      (node (ref "U8") (pin "11") (pinfunction "4Y_11") (pintype "output"))
    )
    (net (code "60") (name "Net-(U4-SDO)") (class "Default")
      (node (ref "U4") (pin "14") (pinfunction "SDO_14") (pintype "output"))
      (node (ref "U8") (pin "2") (pinfunction "1A_2") (pintype "input"))
    )
    (net (code "61") (name "Net-(U5-1Y)") (class "Default")
      (node (ref "R5") (pin "2") (pinfunction "2_2") (pintype "passive"))
      (node (ref "U5") (pin "3") (pinfunction "1Y_3") (pintype "output"))
    )
    (net (code "62") (name "Net-(U6-1Y)") (class "Default")
      (node (ref "R6") (pin "2") (pinfunction "2_2") (pintype "passive"))
      (node (ref "U6") (pin "3") (pinfunction "1Y_3") (pintype "output"))
    )
    (net (code "63") (name "Net-(U7-1Y)") (class "Default")
      (node (ref "R7") (pin "2") (pinfunction "2_2") (pintype "passive"))
      (node (ref "U7") (pin "3") (pinfunction "1Y_3") (pintype "output"))
    )
    (net (code "64") (name "Net-(U8-1Y)") (class "Default")
      (node (ref "R8") (pin "2") (pinfunction "2_2") (pintype "passive"))
      (node (ref "U8") (pin "3") (pinfunction "1Y_3") (pintype "output"))
    )
    (net (code "65") (name "VDD") (class "Default")
      (node (ref "C1") (pin "2") (pinfunction "2_2") (pintype "passive"))
      (node (ref "C3") (pin "2") (pinfunction "2_2") (pintype "passive"))
      (node (ref "C5") (pin "2") (pinfunction "2_2") (pintype "passive"))
      (node (ref "C7") (pin "2") (pinfunction "2_2") (pintype "passive"))
      (node (ref "ES1") (pin "4") (pinfunction "VIN_4") (pintype "passive"))
      (node (ref "ES2") (pin "4") (pinfunction "VIN_4") (pintype "passive"))
      (node (ref "ES3") (pin "4") (pinfunction "VIN_4") (pintype "passive"))
      (node (ref "ES4") (pin "4") (pinfunction "VIN_4") (pintype "passive"))
    )
    (net (code "66") (name "VDD_U1") (class "Default")
      (node (ref "C11") (pin "2") (pinfunction "2_2") (pintype "passive"))
      (node (ref "C15") (pin "2") (pinfunction "2_2") (pintype "passive"))
      (node (ref "C2") (pin "2") (pinfunction "2_2") (pintype "passive"))
      (node (ref "ES1") (pin "3") (pinfunction "VOUT_3") (pintype "passive"))
      (node (ref "R21") (pin "1") (pinfunction "1_1") (pintype "passive"))
      (node (ref "U1") (pin "19") (pinfunction "DVDD_19") (pintype "power_in"))
      (node (ref "U1") (pin "20") (pinfunction "VDD_20") (pintype "power_in"))
      (node (ref "U5") (pin "14") (pinfunction "VCC_14") (pintype "power_in"))
    )
    (net (code "67") (name "VDD_U2") (class "Default")
      (node (ref "C12") (pin "2") (pinfunction "2_2") (pintype "passive"))
      (node (ref "C16") (pin "2") (pinfunction "2_2") (pintype "passive"))
      (node (ref "C4") (pin "2") (pinfunction "2_2") (pintype "passive"))
      (node (ref "ES2") (pin "3") (pinfunction "VOUT_3") (pintype "passive"))
      (node (ref "SB2") (pin "2") (pinfunction "1_2") (pintype "passive"))
      (node (ref "U2") (pin "19") (pinfunction "DVDD_19") (pintype "power_in"))
      (node (ref "U2") (pin "20") (pinfunction "VDD_20") (pintype "power_in"))
      (node (ref "U6") (pin "14") (pinfunction "VCC_14") (pintype "power_in"))
    )
    (net (code "68") (name "VDD_U3") (class "Default")
      (node (ref "C13") (pin "1") (pinfunction "1_1") (pintype "passive"))
      (node (ref "C17") (pin "2") (pinfunction "2_2") (pintype "passive"))
      (node (ref "C6") (pin "2") (pinfunction "2_2") (pintype "passive"))
      (node (ref "ES3") (pin "3") (pinfunction "VOUT_3") (pintype "passive"))
      (node (ref "R23") (pin "1") (pinfunction "1_1") (pintype "passive"))
      (node (ref "U3") (pin "19") (pinfunction "DVDD_19") (pintype "power_in"))
      (node (ref "U3") (pin "20") (pinfunction "VDD_20") (pintype "power_in"))
      (node (ref "U7") (pin "14") (pinfunction "VCC_14") (pintype "power_in"))
    )
    (net (code "69") (name "VDD_U4") (class "Default")
      (node (ref "C14") (pin "2") (pinfunction "2_2") (pintype "passive"))
      (node (ref "C18") (pin "2") (pinfunction "2_2") (pintype "passive"))
      (node (ref "C8") (pin "2") (pinfunction "2_2") (pintype "passive"))
      (node (ref "ES4") (pin "3") (pinfunction "VOUT_3") (pintype "passive"))
      (node (ref "R24") (pin "1") (pinfunction "1_1") (pintype "passive"))
      (node (ref "U4") (pin "19") (pinfunction "DVDD_19") (pintype "power_in"))
      (node (ref "U4") (pin "20") (pinfunction "VDD_20") (pintype "power_in"))
      (node (ref "U8") (pin "14") (pinfunction "VCC_14") (pintype "power_in"))
    )
    (net (code "70") (name "unconnected-(U1-DRDY-Pad18)") (class "Default")
      (node (ref "U1") (pin "18") (pinfunction "DRDY_18") (pintype "output"))
    )
    (net (code "71") (name "unconnected-(U1-N.C.-Pad17)") (class "Default")
      (node (ref "U1") (pin "17") (pinfunction "N.C._17") (pintype "passive"))
    )
    (net (code "72") (name "unconnected-(U2-DRDY-Pad18)") (class "Default")
      (node (ref "U2") (pin "18") (pinfunction "DRDY_18") (pintype "output"))
    )
    (net (code "73") (name "unconnected-(U2-N.C.-Pad17)") (class "Default")
      (node (ref "U2") (pin "17") (pinfunction "N.C._17") (pintype "passive"))
    )
    (net (code "74") (name "unconnected-(U3-DRDY-Pad18)") (class "Default")
      (node (ref "U3") (pin "18") (pinfunction "DRDY_18") (pintype "output"))
    )
    (net (code "75") (name "unconnected-(U3-N.C.-Pad17)") (class "Default")
      (node (ref "U3") (pin "17") (pinfunction "N.C._17") (pintype "passive"))
    )
    (net (code "76") (name "unconnected-(U4-DRDY-Pad18)") (class "Default")
      (node (ref "U4") (pin "18") (pinfunction "DRDY_18") (pintype "output"))
    )
    (net (code "77") (name "unconnected-(U4-N.C.-Pad17)") (class "Default")
      (node (ref "U4") (pin "17") (pinfunction "N.C._17") (pintype "passive"))
    )
  )
)
